# arduino-to-headers-shield.net
KiCad netlist of a schematic drawn in Altium Designer
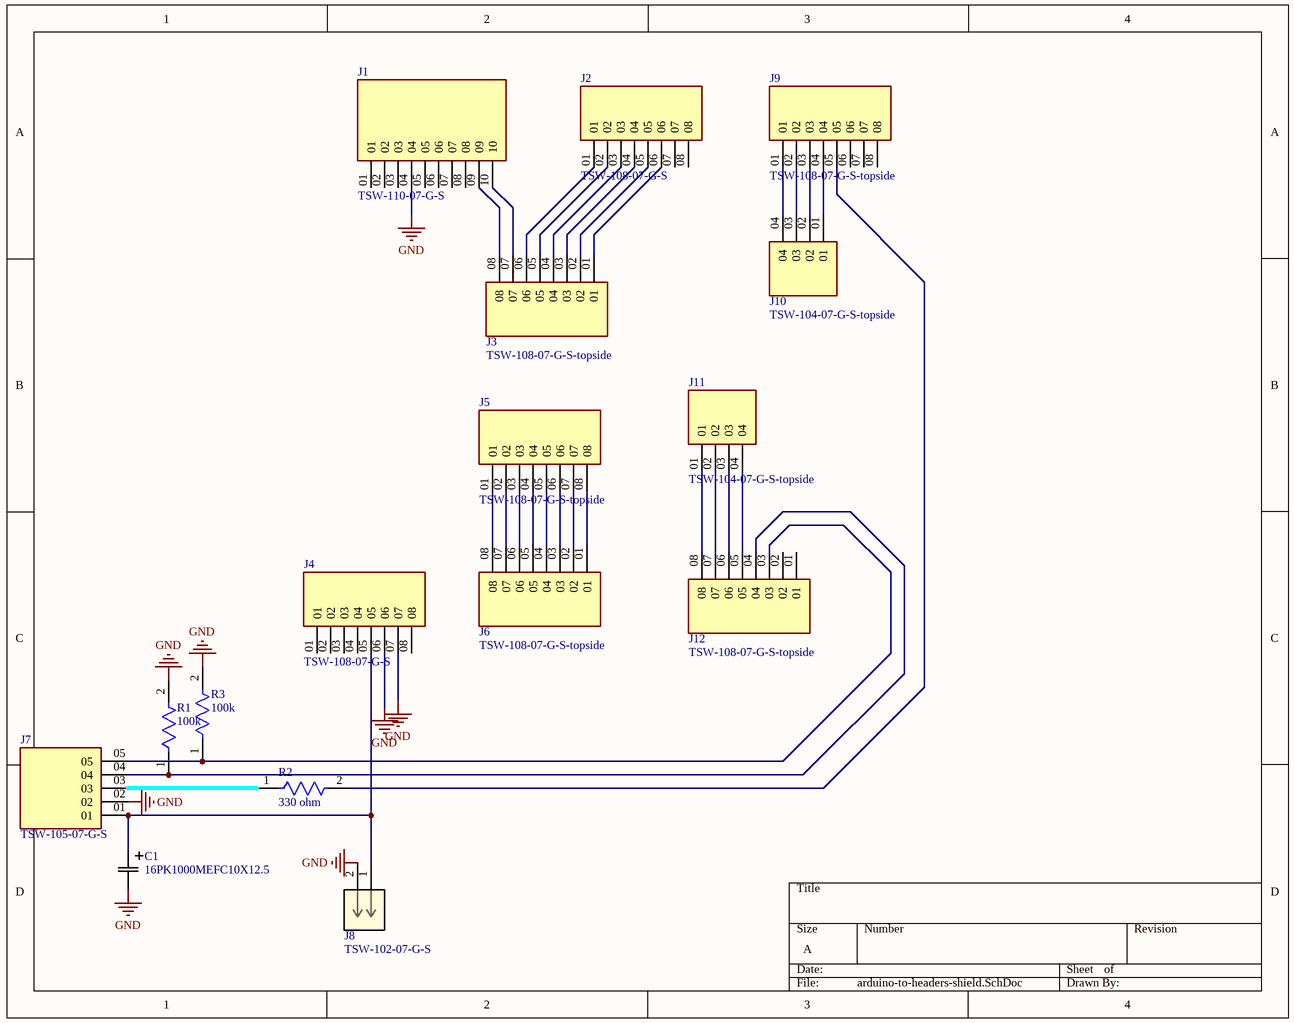
[diagram p0: arduino-to-headers-shield.SchDoc]

(export (version "E")
  (design (tool "Eeschema 10.0.6"))
  (components
    (comp (ref "C1")
      (value "16PK1000MEFC10X12.5")
      (footprint "CAP_PKPZ_10X12P5_LOW_RUB")
      (description "No Description Available")
      (fields (field (name "COPYRIGHT") "Copyright (C) 2024 Ultra Librarian. All rights reserved."))
      (libsource (lib "SchlibLafe") (part "16PK1000MEFC10X12.5"))
    )
    (comp (ref "J1")
      (value "TSW-110-07-G-S")
      (footprint "SAMTEC_TSW-110-07-G-S")
      (fields (field (name "MF") "Samtec Inc."))
      (libsource (lib "SchlibLafe") (part "TSW-110-07-G-S"))
    )
    (comp (ref "J2")
      (value "TSW-108-07-G-S")
      (footprint "SAMTEC_TSW-108-07-G-S")
      (description "TSW - Samtec 2.54mm Pin Header 10.92mm Overall Pin Length (07) - Fast Stock")
      (fields (field (name "MF") "Samtec Inc."))
      (libsource (lib "SchlibLafe") (part "TSW-108-07-G-S"))
    )
    (comp (ref "J3")
      (value "TSW-108-07-G-S-topside")
      (footprint "SAMTEC_TSW-108-07-G-S-topside")
      (description "TSW - Samtec 2.54mm Pin Header 10.92mm Overall Pin Length (07) - Fast Stock")
      (fields (field (name "MF") "Samtec Inc.") (field (name "MP") "TSW-108-07-G-S"))
      (libsource (lib "SchlibLafe") (part "TSW-108-07-G-S-topside"))
    )
    (comp (ref "J4")
      (value "TSW-108-07-G-S")
      (footprint "SAMTEC_TSW-108-07-G-S")
      (description "TSW - Samtec 2.54mm Pin Header 10.92mm Overall Pin Length (07) - Fast Stock")
      (fields (field (name "MF") "Samtec Inc."))
      (libsource (lib "SchlibLafe") (part "TSW-108-07-G-S"))
    )
    (comp (ref "J5")
      (value "TSW-108-07-G-S-topside")
      (footprint "SAMTEC_TSW-108-07-G-S-topside")
      (description "TSW - Samtec 2.54mm Pin Header 10.92mm Overall Pin Length (07) - Fast Stock")
      (fields (field (name "MF") "Samtec Inc.") (field (name "MP") "TSW-108-07-G-S"))
      (libsource (lib "") (part "TSW-108-07-G-S-topside_1"))
    )
    (comp (ref "J6")
      (value "TSW-108-07-G-S-topside")
      (footprint "SAMTEC_TSW-108-07-G-S-topside")
      (description "TSW - Samtec 2.54mm Pin Header 10.92mm Overall Pin Length (07) - Fast Stock")
      (fields (field (name "MF") "Samtec Inc.") (field (name "MP") "TSW-108-07-G-S"))
      (libsource (lib "SchlibLafe") (part "TSW-108-07-G-S-topside"))
    )
    (comp (ref "J7")
      (value "TSW-105-07-G-S")
      (footprint "SAMTEC_TSW-105-07-G-S")
      (fields (field (name "MF") "Samtec Inc."))
      (libsource (lib "SchlibLafe") (part "TSW-105-07-G-S"))
    )
    (comp (ref "J8")
      (value "TSW-102-07-G-S")
      (footprint "TSW-102-07-G-S-topside")
      (description "No Description Available")
      (fields (field (name "COPYRIGHT") "Copyright (C) 2024 Ultra Librarian. All rights reserved."))
      (libsource (lib "SchlibLafe") (part "TSW-102-07-G-S-topside"))
    )
    (comp (ref "J9")
      (value "TSW-108-07-G-S-topside")
      (footprint "SAMTEC_TSW-108-07-G-S-topside")
      (description "TSW - Samtec 2.54mm Pin Header 10.92mm Overall Pin Length (07) - Fast Stock")
      (fields (field (name "MF") "Samtec Inc.") (field (name "MP") "TSW-108-07-G-S"))
      (libsource (lib "") (part "TSW-108-07-G-S-topside_1"))
    )
    (comp (ref "J10")
      (value "TSW-104-07-G-S-topside")
      (footprint "SAMTEC_TSW-104-07-G-S-topside")
      (fields (field (name "MP") "altium_native_batch"))
      (libsource (lib "SchlibLafe") (part "TSW-104-07-G-S-topside"))
    )
    (comp (ref "J11")
      (value "TSW-104-07-G-S-topside")
      (footprint "SAMTEC_TSW-104-07-G-S-topside")
      (fields (field (name "MP") "altium_native_batch"))
      (libsource (lib "") (part "TSW-104-07-G-S-topside_1"))
    )
    (comp (ref "J12")
      (value "TSW-108-07-G-S-topside")
      (footprint "SAMTEC_TSW-108-07-G-S-topside")
      (description "TSW - Samtec 2.54mm Pin Header 10.92mm Overall Pin Length (07) - Fast Stock")
      (fields (field (name "MF") "Samtec Inc.") (field (name "MP") "TSW-108-07-G-S"))
      (libsource (lib "SchlibLafe") (part "TSW-108-07-G-S-topside"))
    )
    (comp (ref "R1")
      (value "100k")
      (footprint "FP-RLR07-MFG")
      (fields (field (name "TOLERANCE") "1%"))
      (libsource (lib "Altium Content Vault") (part "1029c3af85768c4190bb7ad29bc67b5"))
    )
    (comp (ref "R2")
      (value "330 ohm")
      (footprint "FP-RLR07-MFG")
      (fields (field (name "TOLERANCE") "1%"))
      (libsource (lib "Altium Content Vault") (part "1029c3af85768c4190bb7ad29bc67b5"))
    )
    (comp (ref "R3")
      (value "100k")
      (footprint "FP-RLR07-MFG")
      (fields (field (name "TOLERANCE") "1%"))
      (libsource (lib "Altium Content Vault") (part "1029c3af85768c4190bb7ad29bc67b5"))
    )
  )
  (nets
    (net (code "1") (name "GND") (class "Default")
      (node (ref "C1") (pin "2") (pinfunction "2_2") (pintype "passive"))
      (node (ref "J1") (pin "04") (pinfunction "04_04") (pintype "passive"))
      (node (ref "J4") (pin "06") (pinfunction "06_06") (pintype "passive"))
      (node (ref "J4") (pin "07") (pinfunction "07_07") (pintype "passive"))
      (node (ref "J7") (pin "02") (pinfunction "02_02") (pintype "passive"))
      (node (ref "J8") (pin "2") (pinfunction "2_2") (pintype "passive"))
      (node (ref "R1") (pin "2") (pinfunction "2_2") (pintype "passive"))
      (node (ref "R3") (pin "2") (pinfunction "2_2") (pintype "passive"))
    )
    (net (code "2") (name "Net-(C1-Pad1)") (class "Default")
      (node (ref "C1") (pin "1") (pinfunction "1_1") (pintype "passive"))
      (node (ref "J4") (pin "05") (pinfunction "05_05") (pintype "passive"))
      (node (ref "J7") (pin "01") (pinfunction "01_01") (pintype "passive"))
      (node (ref "J8") (pin "1") (pinfunction "1_1") (pintype "passive"))
    )
    (net (code "3") (name "Net-(J1-Pad09)") (class "Default")
      (node (ref "J1") (pin "09") (pinfunction "09_09") (pintype "passive"))
      (node (ref "J3") (pin "08") (pinfunction "08_08") (pintype "passive"))
    )
    (net (code "4") (name "Net-(J1-Pad10)") (class "Default")
      (node (ref "J1") (pin "10") (pinfunction "10_10") (pintype "passive"))
      (node (ref "J3") (pin "07") (pinfunction "07_07") (pintype "passive"))
    )
    (net (code "5") (name "Net-(J2-Pad01)") (class "Default")
      (node (ref "J2") (pin "01") (pinfunction "01_01") (pintype "passive"))
      (node (ref "J3") (pin "06") (pinfunction "06_06") (pintype "passive"))
    )
    (net (code "6") (name "Net-(J2-Pad02)") (class "Default")
      (node (ref "J2") (pin "02") (pinfunction "02_02") (pintype "passive"))
      (node (ref "J3") (pin "05") (pinfunction "05_05") (pintype "passive"))
    )
    (net (code "7") (name "Net-(J2-Pad03)") (class "Default")
      (node (ref "J2") (pin "03") (pinfunction "03_03") (pintype "passive"))
      (node (ref "J3") (pin "04") (pinfunction "04_04") (pintype "passive"))
    )
    (net (code "8") (name "Net-(J2-Pad04)") (class "Default")
      (node (ref "J2") (pin "04") (pinfunction "04_04") (pintype "passive"))
      (node (ref "J3") (pin "03") (pinfunction "03_03") (pintype "passive"))
    )
    (net (code "9") (name "Net-(J2-Pad05)") (class "Default")
      (node (ref "J2") (pin "05") (pinfunction "05_05") (pintype "passive"))
      (node (ref "J3") (pin "02") (pinfunction "02_02") (pintype "passive"))
    )
    (net (code "10") (name "Net-(J2-Pad06)") (class "Default")
      (node (ref "J2") (pin "06") (pinfunction "06_06") (pintype "passive"))
      (node (ref "J3") (pin "01") (pinfunction "01_01") (pintype "passive"))
    )
    (net (code "11") (name "Net-(J5-Pad01)") (class "Default")
      (node (ref "J5") (pin "01") (pinfunction "01_01") (pintype "passive"))
      (node (ref "J6") (pin "08") (pinfunction "08_08") (pintype "passive"))
    )
    (net (code "12") (name "Net-(J5-Pad02)") (class "Default")
      (node (ref "J5") (pin "02") (pinfunction "02_02") (pintype "passive"))
      (node (ref "J6") (pin "07") (pinfunction "07_07") (pintype "passive"))
    )
    (net (code "13") (name "Net-(J5-Pad03)") (class "Default")
      (node (ref "J5") (pin "03") (pinfunction "03_03") (pintype "passive"))
      (node (ref "J6") (pin "06") (pinfunction "06_06") (pintype "passive"))
    )
    (net (code "14") (name "Net-(J5-Pad04)") (class "Default")
      (node (ref "J5") (pin "04") (pinfunction "04_04") (pintype "passive"))
      (node (ref "J6") (pin "05") (pinfunction "05_05") (pintype "passive"))
    )
    (net (code "15") (name "Net-(J5-Pad05)") (class "Default")
      (node (ref "J5") (pin "05") (pinfunction "05_05") (pintype "passive"))
      (node (ref "J6") (pin "04") (pinfunction "04_04") (pintype "passive"))
    )
    (net (code "16") (name "Net-(J5-Pad06)") (class "Default")
      (node (ref "J5") (pin "06") (pinfunction "06_06") (pintype "passive"))
      (node (ref "J6") (pin "03") (pinfunction "03_03") (pintype "passive"))
    )
    (net (code "17") (name "Net-(J5-Pad07)") (class "Default")
      (node (ref "J5") (pin "07") (pinfunction "07_07") (pintype "passive"))
      (node (ref "J6") (pin "02") (pinfunction "02_02") (pintype "passive"))
    )
    (net (code "18") (name "Net-(J5-Pad08)") (class "Default")
      (node (ref "J5") (pin "08") (pinfunction "08_08") (pintype "passive"))
      (node (ref "J6") (pin "01") (pinfunction "01_01") (pintype "passive"))
    )
    (net (code "19") (name "Net-(J7-Pad03)") (class "Default")
      (node (ref "J7") (pin "03") (pinfunction "03_03") (pintype "passive"))
      (node (ref "R2") (pin "1") (pinfunction "1_1") (pintype "passive"))
    )
    (net (code "20") (name "Net-(J9-Pad05)") (class "Default")
      (node (ref "J9") (pin "05") (pinfunction "05_05") (pintype "passive"))
      (node (ref "R2") (pin "2") (pinfunction "2_2") (pintype "passive"))
    )
    (net (code "21") (name "Net-(J10-Pad01)") (class "Default")
      (node (ref "J10") (pin "01") (pinfunction "01_01") (pintype "passive"))
      (node (ref "J9") (pin "04") (pinfunction "04_04") (pintype "passive"))
    )
    (net (code "22") (name "Net-(J10-Pad02)") (class "Default")
      (node (ref "J10") (pin "02") (pinfunction "02_02") (pintype "passive"))
      (node (ref "J9") (pin "03") (pinfunction "03_03") (pintype "passive"))
    )
    (net (code "23") (name "Net-(J10-Pad03)") (class "Default")
      (node (ref "J10") (pin "03") (pinfunction "03_03") (pintype "passive"))
      (node (ref "J9") (pin "02") (pinfunction "02_02") (pintype "passive"))
    )
    (net (code "24") (name "Net-(J10-Pad04)") (class "Default")
      (node (ref "J10") (pin "04") (pinfunction "04_04") (pintype "passive"))
      (node (ref "J9") (pin "01") (pinfunction "01_01") (pintype "passive"))
    )
    (net (code "25") (name "Net-(J11-Pad01)") (class "Default")
      (node (ref "J11") (pin "01") (pinfunction "01_01") (pintype "passive"))
      (node (ref "J12") (pin "08") (pinfunction "08_08") (pintype "passive"))
    )
    (net (code "26") (name "Net-(J11-Pad02)") (class "Default")
      (node (ref "J11") (pin "02") (pinfunction "02_02") (pintype "passive"))
      (node (ref "J12") (pin "07") (pinfunction "07_07") (pintype "passive"))
    )
    (net (code "27") (name "Net-(J11-Pad03)") (class "Default")
      (node (ref "J11") (pin "03") (pinfunction "03_03") (pintype "passive"))
      (node (ref "J12") (pin "06") (pinfunction "06_06") (pintype "passive"))
    )
    (net (code "28") (name "Net-(J11-Pad04)") (class "Default")
      (node (ref "J11") (pin "04") (pinfunction "04_04") (pintype "passive"))
      (node (ref "J12") (pin "05") (pinfunction "05_05") (pintype "passive"))
    )
    (net (code "29") (name "Net-(J12-Pad03)") (class "Default")
      (node (ref "J12") (pin "03") (pinfunction "03_03") (pintype "passive"))
      (node (ref "J7") (pin "05") (pinfunction "05_05") (pintype "passive"))
      (node (ref "R3") (pin "1") (pinfunction "1_1") (pintype "passive"))
    )
    (net (code "30") (name "Net-(J12-Pad04)") (class "Default")
      (node (ref "J12") (pin "04") (pinfunction "04_04") (pintype "passive"))
      (node (ref "J7") (pin "04") (pinfunction "04_04") (pintype "passive"))
      (node (ref "R1") (pin "1") (pinfunction "1_1") (pintype "passive"))
    )
    (net (code "31") (name "unconnected-(J1-Pad01)") (class "Default")
      (node (ref "J1") (pin "01") (pinfunction "01_01") (pintype "passive"))
    )
    (net (code "32") (name "unconnected-(J1-Pad02)") (class "Default")
      (node (ref "J1") (pin "02") (pinfunction "02_02") (pintype "passive"))
    )
    (net (code "33") (name "unconnected-(J1-Pad03)") (class "Default")
      (node (ref "J1") (pin "03") (pinfunction "03_03") (pintype "passive"))
    )
    (net (code "34") (name "unconnected-(J1-Pad05)") (class "Default")
      (node (ref "J1") (pin "05") (pinfunction "05_05") (pintype "passive"))
    )
    (net (code "35") (name "unconnected-(J1-Pad06)") (class "Default")
      (node (ref "J1") (pin "06") (pinfunction "06_06") (pintype "passive"))
    )
    (net (code "36") (name "unconnected-(J1-Pad07)") (class "Default")
      (node (ref "J1") (pin "07") (pinfunction "07_07") (pintype "passive"))
    )
    (net (code "37") (name "unconnected-(J1-Pad08)") (class "Default")
      (node (ref "J1") (pin "08") (pinfunction "08_08") (pintype "passive"))
    )
    (net (code "38") (name "unconnected-(J2-Pad07)") (class "Default")
      (node (ref "J2") (pin "07") (pinfunction "07_07") (pintype "passive"))
    )
    (net (code "39") (name "unconnected-(J2-Pad08)") (class "Default")
      (node (ref "J2") (pin "08") (pinfunction "08_08") (pintype "passive"))
    )
    (net (code "40") (name "unconnected-(J4-Pad01)") (class "Default")
      (node (ref "J4") (pin "01") (pinfunction "01_01") (pintype "passive"))
    )
    (net (code "41") (name "unconnected-(J4-Pad02)") (class "Default")
      (node (ref "J4") (pin "02") (pinfunction "02_02") (pintype "passive"))
    )
    (net (code "42") (name "unconnected-(J4-Pad03)") (class "Default")
      (node (ref "J4") (pin "03") (pinfunction "03_03") (pintype "passive"))
    )
    (net (code "43") (name "unconnected-(J4-Pad04)") (class "Default")
      (node (ref "J4") (pin "04") (pinfunction "04_04") (pintype "passive"))
    )
    (net (code "44") (name "unconnected-(J4-Pad08)") (class "Default")
      (node (ref "J4") (pin "08") (pinfunction "08_08") (pintype "passive"))
    )
    (net (code "45") (name "unconnected-(J9-Pad06)") (class "Default")
      (node (ref "J9") (pin "06") (pinfunction "06_06") (pintype "passive"))
    )
    (net (code "46") (name "unconnected-(J9-Pad07)") (class "Default")
      (node (ref "J9") (pin "07") (pinfunction "07_07") (pintype "passive"))
    )
    (net (code "47") (name "unconnected-(J9-Pad08)") (class "Default")
      (node (ref "J9") (pin "08") (pinfunction "08_08") (pintype "passive"))
    )
    (net (code "48") (name "unconnected-(J12-Pad01)") (class "Default")
      (node (ref "J12") (pin "01") (pinfunction "01_01") (pintype "passive"))
    )
    (net (code "49") (name "unconnected-(J12-Pad02)") (class "Default")
      (node (ref "J12") (pin "02") (pinfunction "02_02") (pintype "passive"))
    )
  )
)
